# ngh-dram.net
KiCad netlist of a schematic drawn in Altium Designer
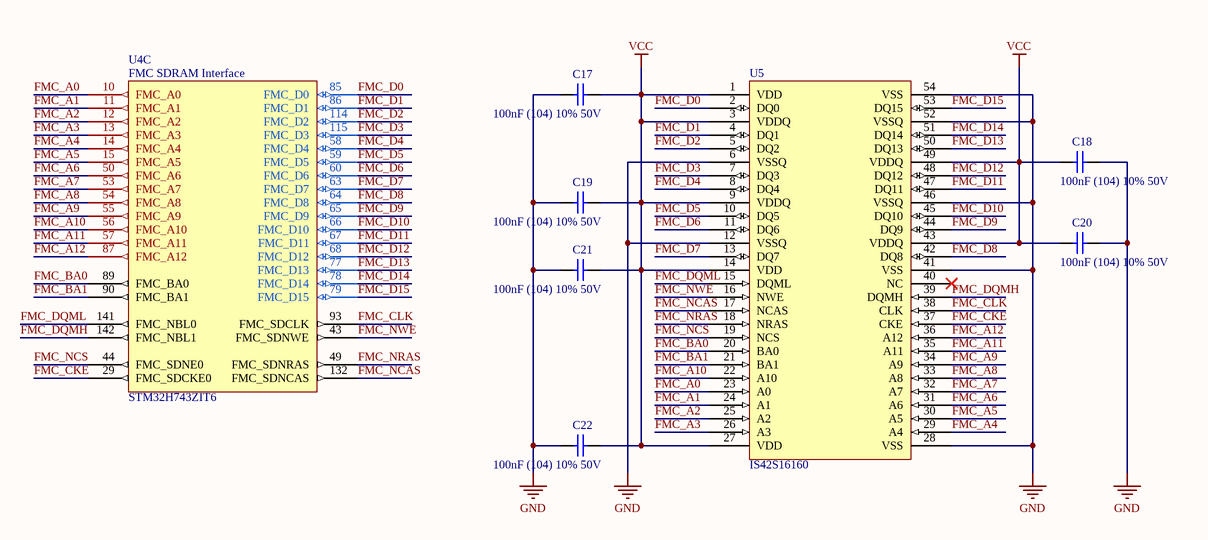
[diagram p0: ngh-dram.SchDoc]

(export (version "E")
  (design (tool "Eeschema 10.0.6"))
  (components
    (comp (ref "C17")
      (value "100nF (104) 10% 50V")
      (footprint "0603_C")
      (description "贴片电容")
      (libsource (lib "Miscellaneous Devices LC") (part "0603 100nF (104) 10% 50V"))
    )
    (comp (ref "C18")
      (value "100nF (104) 10% 50V")
      (footprint "0603_C")
      (description "贴片电容")
      (libsource (lib "Miscellaneous Devices LC") (part "0603 100nF (104) 10% 50V"))
    )
    (comp (ref "C19")
      (value "100nF (104) 10% 50V")
      (footprint "0603_C")
      (description "贴片电容")
      (libsource (lib "Miscellaneous Devices LC") (part "0603 100nF (104) 10% 50V"))
    )
    (comp (ref "C20")
      (value "100nF (104) 10% 50V")
      (footprint "0603_C")
      (description "贴片电容")
      (libsource (lib "Miscellaneous Devices LC") (part "0603 100nF (104) 10% 50V"))
    )
    (comp (ref "C21")
      (value "100nF (104) 10% 50V")
      (footprint "0603_C")
      (description "贴片电容")
      (libsource (lib "Miscellaneous Devices LC") (part "0603 100nF (104) 10% 50V"))
    )
    (comp (ref "C22")
      (value "100nF (104) 10% 50V")
      (footprint "0603_C")
      (description "贴片电容")
      (libsource (lib "Miscellaneous Devices LC") (part "0603 100nF (104) 10% 50V"))
    )
    (comp (ref "U4")
      (value "STM32H743ZIT6")
      (footprint "LQFP-144_20x20")
      (libsource (lib "STM32H743ZI") (part "STM32H743ZIT6"))
    )
    (comp (ref "U5")
      (value "IS42S16160")
      (footprint "TSOP54-II")
      (libsource (lib "ISSI_SDRAM") (part "IS42S16160"))
    )
  )
  (nets
    (net (code "1") (name "/FMC_A0") (class "Default")
      (node (ref "U4") (pin "10") (pinfunction "FMC_A0_10") (pintype "output"))
      (node (ref "U5") (pin "23") (pinfunction "A0_23") (pintype "input"))
    )
    (net (code "2") (name "/FMC_A1") (class "Default")
      (node (ref "U4") (pin "11") (pinfunction "FMC_A1_11") (pintype "output"))
      (node (ref "U5") (pin "24") (pinfunction "A1_24") (pintype "input"))
    )
    (net (code "3") (name "/FMC_A2") (class "Default")
      (node (ref "U4") (pin "12") (pinfunction "FMC_A2_12") (pintype "output"))
      (node (ref "U5") (pin "25") (pinfunction "A2_25") (pintype "input"))
    )
    (net (code "4") (name "/FMC_A3") (class "Default")
      (node (ref "U4") (pin "13") (pinfunction "FMC_A3_13") (pintype "output"))
      (node (ref "U5") (pin "26") (pinfunction "A3_26") (pintype "input"))
    )
    (net (code "5") (name "/FMC_A4") (class "Default")
      (node (ref "U4") (pin "14") (pinfunction "FMC_A4_14") (pintype "output"))
      (node (ref "U5") (pin "29") (pinfunction "A4_29") (pintype "input"))
    )
    (net (code "6") (name "/FMC_A5") (class "Default")
      (node (ref "U4") (pin "15") (pinfunction "FMC_A5_15") (pintype "output"))
      (node (ref "U5") (pin "30") (pinfunction "A5_30") (pintype "input"))
    )
    (net (code "7") (name "/FMC_A6") (class "Default")
      (node (ref "U4") (pin "50") (pinfunction "FMC_A6_50") (pintype "output"))
      (node (ref "U5") (pin "31") (pinfunction "A6_31") (pintype "input"))
    )
    (net (code "8") (name "/FMC_A7") (class "Default")
      (node (ref "U4") (pin "53") (pinfunction "FMC_A7_53") (pintype "output"))
      (node (ref "U5") (pin "32") (pinfunction "A7_32") (pintype "input"))
    )
    (net (code "9") (name "/FMC_A8") (class "Default")
      (node (ref "U4") (pin "54") (pinfunction "FMC_A8_54") (pintype "output"))
      (node (ref "U5") (pin "33") (pinfunction "A8_33") (pintype "input"))
    )
    (net (code "10") (name "/FMC_A9") (class "Default")
      (node (ref "U4") (pin "55") (pinfunction "FMC_A9_55") (pintype "output"))
      (node (ref "U5") (pin "34") (pinfunction "A9_34") (pintype "input"))
    )
    (net (code "11") (name "/FMC_A10") (class "Default")
      (node (ref "U4") (pin "56") (pinfunction "FMC_A10_56") (pintype "output"))
      (node (ref "U5") (pin "22") (pinfunction "A10_22") (pintype "input"))
    )
    (net (code "12") (name "/FMC_A11") (class "Default")
      (node (ref "U4") (pin "57") (pinfunction "FMC_A11_57") (pintype "output"))
      (node (ref "U5") (pin "35") (pinfunction "A11_35") (pintype "input"))
    )
    (net (code "13") (name "/FMC_A12") (class "Default")
      (node (ref "U4") (pin "87") (pinfunction "FMC_A12_87") (pintype "output"))
      (node (ref "U5") (pin "36") (pinfunction "A12_36") (pintype "input"))
    )
    (net (code "14") (name "/FMC_BA0") (class "Default")
      (node (ref "U4") (pin "89") (pinfunction "FMC_BA0_89") (pintype "output"))
      (node (ref "U5") (pin "20") (pinfunction "BA0_20") (pintype "input"))
    )
    (net (code "15") (name "/FMC_BA1") (class "Default")
      (node (ref "U4") (pin "90") (pinfunction "FMC_BA1_90") (pintype "output"))
      (node (ref "U5") (pin "21") (pinfunction "BA1_21") (pintype "input"))
    )
    (net (code "16") (name "/FMC_CKE") (class "Default")
      (node (ref "U4") (pin "29") (pinfunction "FMC_SDCKE0_29") (pintype "output"))
      (node (ref "U5") (pin "37") (pinfunction "CKE_37") (pintype "input"))
    )
    (net (code "17") (name "/FMC_CLK") (class "Default")
      (node (ref "U4") (pin "93") (pinfunction "FMC_SDCLK_93") (pintype "output"))
      (node (ref "U5") (pin "38") (pinfunction "CLK_38") (pintype "input"))
    )
    (net (code "18") (name "/FMC_D0") (class "Default")
      (node (ref "U4") (pin "85") (pinfunction "FMC_D0_85") (pintype "bidirectional"))
      (node (ref "U5") (pin "2") (pinfunction "DQ0_2") (pintype "bidirectional"))
    )
    (net (code "19") (name "/FMC_D1") (class "Default")
      (node (ref "U4") (pin "86") (pinfunction "FMC_D1_86") (pintype "bidirectional"))
      (node (ref "U5") (pin "4") (pinfunction "DQ1_4") (pintype "bidirectional"))
    )
    (net (code "20") (name "/FMC_D2") (class "Default")
      (node (ref "U4") (pin "114") (pinfunction "FMC_D2_114") (pintype "bidirectional"))
      (node (ref "U5") (pin "5") (pinfunction "DQ2_5") (pintype "bidirectional"))
    )
    (net (code "21") (name "/FMC_D3") (class "Default")
      (node (ref "U4") (pin "115") (pinfunction "FMC_D3_115") (pintype "bidirectional"))
      (node (ref "U5") (pin "7") (pinfunction "DQ3_7") (pintype "bidirectional"))
    )
    (net (code "22") (name "/FMC_D4") (class "Default")
      (node (ref "U4") (pin "58") (pinfunction "FMC_D4_58") (pintype "bidirectional"))
      (node (ref "U5") (pin "8") (pinfunction "DQ4_8") (pintype "bidirectional"))
    )
    (net (code "23") (name "/FMC_D5") (class "Default")
      (node (ref "U4") (pin "59") (pinfunction "FMC_D5_59") (pintype "bidirectional"))
      (node (ref "U5") (pin "10") (pinfunction "DQ5_10") (pintype "bidirectional"))
    )
    (net (code "24") (name "/FMC_D6") (class "Default")
      (node (ref "U4") (pin "60") (pinfunction "FMC_D6_60") (pintype "bidirectional"))
      (node (ref "U5") (pin "11") (pinfunction "DQ6_11") (pintype "bidirectional"))
    )
    (net (code "25") (name "/FMC_D7") (class "Default")
      (node (ref "U4") (pin "63") (pinfunction "FMC_D7_63") (pintype "bidirectional"))
      (node (ref "U5") (pin "13") (pinfunction "DQ7_13") (pintype "bidirectional"))
    )
    (net (code "26") (name "/FMC_D8") (class "Default")
      (node (ref "U4") (pin "64") (pinfunction "FMC_D8_64") (pintype "bidirectional"))
      (node (ref "U5") (pin "42") (pinfunction "DQ8_42") (pintype "bidirectional"))
    )
    (net (code "27") (name "/FMC_D9") (class "Default")
      (node (ref "U4") (pin "65") (pinfunction "FMC_D9_65") (pintype "bidirectional"))
      (node (ref "U5") (pin "44") (pinfunction "DQ9_44") (pintype "bidirectional"))
    )
    (net (code "28") (name "/FMC_D10") (class "Default")
      (node (ref "U4") (pin "66") (pinfunction "FMC_D10_66") (pintype "bidirectional"))
      (node (ref "U5") (pin "45") (pinfunction "DQ10_45") (pintype "bidirectional"))
    )
    (net (code "29") (name "/FMC_D11") (class "Default")
      (node (ref "U4") (pin "67") (pinfunction "FMC_D11_67") (pintype "bidirectional"))
      (node (ref "U5") (pin "47") (pinfunction "DQ11_47") (pintype "bidirectional"))
    )
    (net (code "30") (name "/FMC_D12") (class "Default")
      (node (ref "U4") (pin "68") (pinfunction "FMC_D12_68") (pintype "bidirectional"))
      (node (ref "U5") (pin "48") (pinfunction "DQ12_48") (pintype "bidirectional"))
    )
    (net (code "31") (name "/FMC_D13") (class "Default")
      (node (ref "U4") (pin "77") (pinfunction "FMC_D13_77") (pintype "bidirectional"))
      (node (ref "U5") (pin "50") (pinfunction "DQ13_50") (pintype "bidirectional"))
    )
    (net (code "32") (name "/FMC_D14") (class "Default")
      (node (ref "U4") (pin "78") (pinfunction "FMC_D14_78") (pintype "bidirectional"))
      (node (ref "U5") (pin "51") (pinfunction "DQ14_51") (pintype "bidirectional"))
    )
    (net (code "33") (name "/FMC_D15") (class "Default")
      (node (ref "U4") (pin "79") (pinfunction "FMC_D15_79") (pintype "bidirectional"))
      (node (ref "U5") (pin "53") (pinfunction "DQ15_53") (pintype "bidirectional"))
    )
    (net (code "34") (name "/FMC_DQMH") (class "Default")
      (node (ref "U4") (pin "142") (pinfunction "FMC_NBL1_142") (pintype "output"))
      (node (ref "U5") (pin "39") (pinfunction "DQMH_39") (pintype "input"))
    )
    (net (code "35") (name "/FMC_DQML") (class "Default")
      (node (ref "U4") (pin "141") (pinfunction "FMC_NBL0_141") (pintype "output"))
      (node (ref "U5") (pin "15") (pinfunction "DQML_15") (pintype "input"))
    )
    (net (code "36") (name "/FMC_NCAS") (class "Default")
      (node (ref "U4") (pin "132") (pinfunction "FMC_SDNCAS_132") (pintype "output"))
      (node (ref "U5") (pin "17") (pinfunction "NCAS_17") (pintype "input"))
    )
    (net (code "37") (name "/FMC_NCS") (class "Default")
      (node (ref "U4") (pin "44") (pinfunction "FMC_SDNE0_44") (pintype "output"))
      (node (ref "U5") (pin "19") (pinfunction "NCS_19") (pintype "input"))
    )
    (net (code "38") (name "/FMC_NRAS") (class "Default")
      (node (ref "U4") (pin "49") (pinfunction "FMC_SDNRAS_49") (pintype "output"))
      (node (ref "U5") (pin "18") (pinfunction "NRAS_18") (pintype "input"))
    )
    (net (code "39") (name "/FMC_NWE") (class "Default")
      (node (ref "U4") (pin "43") (pinfunction "FMC_SDNWE_43") (pintype "output"))
      (node (ref "U5") (pin "16") (pinfunction "NWE_16") (pintype "input"))
    )
    (net (code "40") (name "GND") (class "Default")
      (node (ref "C17") (pin "2") (pinfunction "2_2") (pintype "passive"))
      (node (ref "C18") (pin "1") (pinfunction "1_1") (pintype "passive"))
      (node (ref "C19") (pin "2") (pinfunction "2_2") (pintype "passive"))
      (node (ref "C20") (pin "1") (pinfunction "1_1") (pintype "passive"))
      (node (ref "C21") (pin "2") (pinfunction "2_2") (pintype "passive"))
      (node (ref "C22") (pin "2") (pinfunction "2_2") (pintype "passive"))
      (node (ref "U5") (pin "12") (pinfunction "VSSQ_12") (pintype "power_in"))
      (node (ref "U5") (pin "28") (pinfunction "VSS_28") (pintype "power_in"))
      (node (ref "U5") (pin "41") (pinfunction "VSS_41") (pintype "power_in"))
      (node (ref "U5") (pin "46") (pinfunction "VSSQ_46") (pintype "power_in"))
      (node (ref "U5") (pin "52") (pinfunction "VSSQ_52") (pintype "power_in"))
      (node (ref "U5") (pin "54") (pinfunction "VSS_54") (pintype "power_in"))
      (node (ref "U5") (pin "6") (pinfunction "VSSQ_6") (pintype "power_in"))
    )
    (net (code "41") (name "VCC") (class "Default")
      (node (ref "C17") (pin "1") (pinfunction "1_1") (pintype "passive"))
      (node (ref "C18") (pin "2") (pinfunction "2_2") (pintype "passive"))
      (node (ref "C19") (pin "1") (pinfunction "1_1") (pintype "passive"))
      (node (ref "C20") (pin "2") (pinfunction "2_2") (pintype "passive"))
      (node (ref "C21") (pin "1") (pinfunction "1_1") (pintype "passive"))
      (node (ref "C22") (pin "1") (pinfunction "1_1") (pintype "passive"))
      (node (ref "U5") (pin "1") (pinfunction "VDD_1") (pintype "power_in"))
      (node (ref "U5") (pin "14") (pinfunction "VDD_14") (pintype "power_in"))
      (node (ref "U5") (pin "27") (pinfunction "VDD_27") (pintype "power_in"))
      (node (ref "U5") (pin "3") (pinfunction "VDDQ_3") (pintype "power_in"))
      (node (ref "U5") (pin "43") (pinfunction "VDDQ_43") (pintype "power_in"))
      (node (ref "U5") (pin "49") (pinfunction "VDDQ_49") (pintype "power_in"))
      (node (ref "U5") (pin "9") (pinfunction "VDDQ_9") (pintype "power_in"))
    )
    (net (code "42") (name "unconnected-(U5-NC-Pad40)") (class "Default")
      (node (ref "U5") (pin "40") (pinfunction "NC_40") (pintype "passive+no_connect"))
    )
  )
)
